# main.net
KiCad netlist of a schematic drawn in Altium Designer
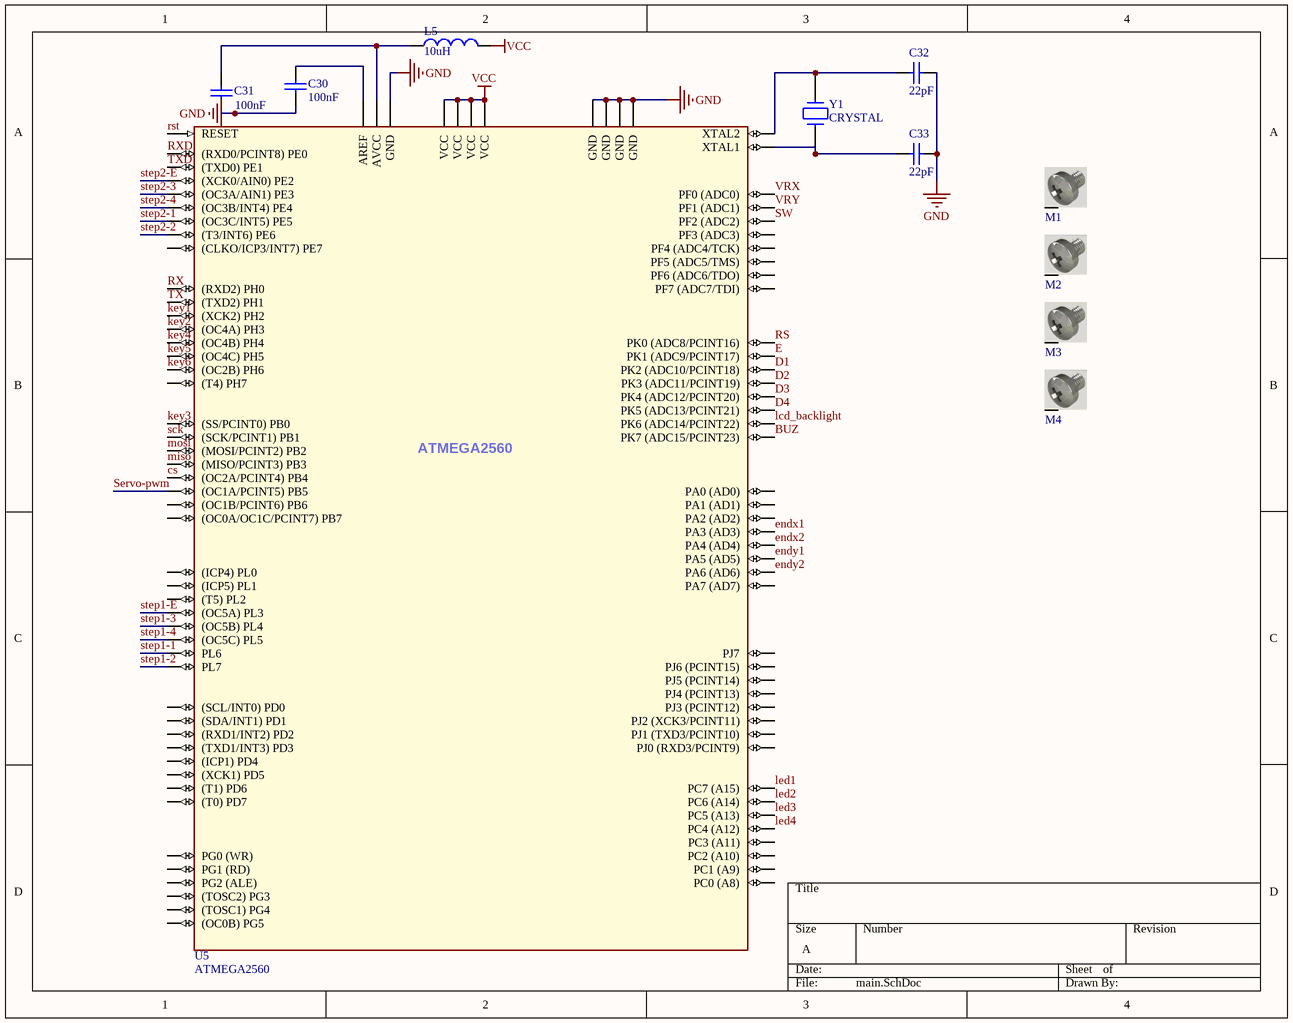
[diagram p0: main.SchDoc]

(export (version "E")
  (design (tool "Eeschema 10.0.6"))
  (components
    (comp (ref "C30")
      (value "100nF")
      (footprint "CAP 1206/3216 - 0.8MM")
      (description "CAP-100Nf")
      (fields (field (name "Comment") "Cap"))
      (libsource (lib "Altium library (www.AVRelec.com)") (part "Cap ceramic"))
    )
    (comp (ref "C31")
      (value "100nF")
      (footprint "CAP 1206/3216 - 0.8MM")
      (description "CAP-100Nf")
      (fields (field (name "Comment") "Cap"))
      (libsource (lib "Altium library (www.AVRelec.com)") (part "Cap ceramic"))
    )
    (comp (ref "C32")
      (value "22pF")
      (footprint "CAP 1206/3216 - 0.8MM")
      (description "CAP-100Nf")
      (fields (field (name "Comment") "Cap"))
      (libsource (lib "Altium library (www.AVRelec.com)") (part "Cap ceramic"))
    )
    (comp (ref "C33")
      (value "22pF")
      (footprint "CAP 1206/3216 - 0.8MM")
      (description "CAP-100Nf")
      (fields (field (name "Comment") "Cap"))
      (libsource (lib "Altium library (www.AVRelec.com)") (part "Cap ceramic"))
    )
    (comp (ref "L5")
      (value "10uH")
      (footprint "C1210_M")
      (description "Inductor")
      (fields (field (name "PUBLISHER") "Altium Limited"))
      (libsource (lib "Miscellaneous Devices") (part "Inductor"))
    )
    (comp (ref "M1")
      (value "Screw")
      (footprint "Board Screw")
      (description "Board Screw With Spacer")
      (libsource (lib "My Library") (part "Board Screw"))
    )
    (comp (ref "M2")
      (value "Screw")
      (footprint "Board Screw")
      (description "Board Screw With Spacer")
      (libsource (lib "My Library") (part "Board Screw"))
    )
    (comp (ref "M3")
      (value "Screw")
      (footprint "Board Screw")
      (description "Board Screw With Spacer")
      (libsource (lib "My Library") (part "Board Screw"))
    )
    (comp (ref "M4")
      (value "Screw")
      (footprint "Board Screw")
      (description "Board Screw With Spacer")
      (libsource (lib "My Library") (part "Board Screw"))
    )
    (comp (ref "U5")
      (value "ATMEGA2560")
      (footprint "MY_ATMEGA2560")
      (description "AVR 256K Bytes of In-System Programmable Flash Memory")
      (libsource (lib "Altium library (www.AVRelec.com)") (part "ATMEGA2560"))
    )
    (comp (ref "Y1")
      (value "CRYSTAL")
      (footprint "My_Crystal")
      (description "Crystal")
      (libsource (lib "Altium library (www.AVRelec.com)") (part "CRYSTAL"))
    )
  )
  (nets
    (net (code "1") (name "/BUZ") (class "Default")
      (node (ref "U5") (pin "82") (pinfunction "PK7_(ADC15/PCINT23)_82") (pintype "bidirectional"))
    )
    (net (code "2") (name "/D1") (class "Default")
      (node (ref "U5") (pin "87") (pinfunction "PK2_(ADC10/PCINT18)_87") (pintype "bidirectional"))
    )
    (net (code "3") (name "/D2") (class "Default")
      (node (ref "U5") (pin "86") (pinfunction "PK3_(ADC11/PCINT19)_86") (pintype "bidirectional"))
    )
    (net (code "4") (name "/D3") (class "Default")
      (node (ref "U5") (pin "85") (pinfunction "PK4_(ADC12/PCINT20)_85") (pintype "bidirectional"))
    )
    (net (code "5") (name "/D4") (class "Default")
      (node (ref "U5") (pin "84") (pinfunction "PK5_(ADC13/PCINT21)_84") (pintype "bidirectional"))
    )
    (net (code "6") (name "/E") (class "Default")
      (node (ref "U5") (pin "88") (pinfunction "PK1_(ADC9/PCINT17)_88") (pintype "bidirectional"))
    )
    (net (code "7") (name "/RS") (class "Default")
      (node (ref "U5") (pin "89") (pinfunction "PK0_(ADC8/PCINT16)_89") (pintype "bidirectional"))
    )
    (net (code "8") (name "/RX") (class "Default")
      (node (ref "U5") (pin "12") (pinfunction "(RXD2)_PH0_12") (pintype "bidirectional"))
    )
    (net (code "9") (name "/RXD") (class "Default")
      (node (ref "U5") (pin "2") (pinfunction "(RXD0/PCINT8)_PE0_2") (pintype "bidirectional"))
    )
    (net (code "10") (name "/SW") (class "Default")
      (node (ref "U5") (pin "95") (pinfunction "PF2_(ADC2)_95") (pintype "bidirectional"))
    )
    (net (code "11") (name "/Servo-pwm") (class "Default")
      (node (ref "U5") (pin "24") (pinfunction "(OC1A/PCINT5)_PB5_24") (pintype "bidirectional"))
    )
    (net (code "12") (name "/TX") (class "Default")
      (node (ref "U5") (pin "13") (pinfunction "(TXD2)_PH1_13") (pintype "bidirectional"))
    )
    (net (code "13") (name "/TXD") (class "Default")
      (node (ref "U5") (pin "3") (pinfunction "(TXD0)_PE1_3") (pintype "bidirectional"))
    )
    (net (code "14") (name "/VRX") (class "Default")
      (node (ref "U5") (pin "97") (pinfunction "PF0_(ADC0)_97") (pintype "bidirectional"))
    )
    (net (code "15") (name "/VRY") (class "Default")
      (node (ref "U5") (pin "96") (pinfunction "PF1_(ADC1)_96") (pintype "bidirectional"))
    )
    (net (code "16") (name "/cs") (class "Default")
      (node (ref "U5") (pin "23") (pinfunction "(OC2A/PCINT4)_PB4_23") (pintype "bidirectional"))
    )
    (net (code "17") (name "/endx1") (class "Default")
      (node (ref "U5") (pin "75") (pinfunction "PA3_(AD3)_75") (pintype "bidirectional"))
    )
    (net (code "18") (name "/endx2") (class "Default")
      (node (ref "U5") (pin "74") (pinfunction "PA4_(AD4)_74") (pintype "bidirectional"))
    )
    (net (code "19") (name "/endy1") (class "Default")
      (node (ref "U5") (pin "73") (pinfunction "PA5_(AD5)_73") (pintype "bidirectional"))
    )
    (net (code "20") (name "/endy2") (class "Default")
      (node (ref "U5") (pin "72") (pinfunction "PA6_(AD6)_72") (pintype "bidirectional"))
    )
    (net (code "21") (name "/key1") (class "Default")
      (node (ref "U5") (pin "14") (pinfunction "(XCK2)_PH2_14") (pintype "bidirectional"))
    )
    (net (code "22") (name "/key2") (class "Default")
      (node (ref "U5") (pin "15") (pinfunction "(OC4A)_PH3_15") (pintype "bidirectional"))
    )
    (net (code "23") (name "/key3") (class "Default")
      (node (ref "U5") (pin "19") (pinfunction "(SS/PCINT0)_PB0_19") (pintype "bidirectional"))
    )
    (net (code "24") (name "/key4") (class "Default")
      (node (ref "U5") (pin "16") (pinfunction "(OC4B)_PH4_16") (pintype "bidirectional"))
    )
    (net (code "25") (name "/key5") (class "Default")
      (node (ref "U5") (pin "17") (pinfunction "(OC4C)_PH5_17") (pintype "bidirectional"))
    )
    (net (code "26") (name "/key6") (class "Default")
      (node (ref "U5") (pin "18") (pinfunction "(OC2B)_PH6_18") (pintype "bidirectional"))
    )
    (net (code "27") (name "/lcd_backlight") (class "Default")
      (node (ref "U5") (pin "83") (pinfunction "PK6_(ADC14/PCINT22)_83") (pintype "bidirectional"))
    )
    (net (code "28") (name "/led1") (class "Default")
      (node (ref "U5") (pin "60") (pinfunction "PC7_(A15)_60") (pintype "bidirectional"))
    )
    (net (code "29") (name "/led2") (class "Default")
      (node (ref "U5") (pin "59") (pinfunction "PC6_(A14)_59") (pintype "bidirectional"))
    )
    (net (code "30") (name "/led3") (class "Default")
      (node (ref "U5") (pin "58") (pinfunction "PC5_(A13)_58") (pintype "bidirectional"))
    )
    (net (code "31") (name "/led4") (class "Default")
      (node (ref "U5") (pin "57") (pinfunction "PC4_(A12)_57") (pintype "bidirectional"))
    )
    (net (code "32") (name "/miso") (class "Default")
      (node (ref "U5") (pin "22") (pinfunction "(MISO/PCINT3)_PB3_22") (pintype "bidirectional"))
    )
    (net (code "33") (name "/mosi") (class "Default")
      (node (ref "U5") (pin "21") (pinfunction "(MOSI/PCINT2)_PB2_21") (pintype "bidirectional"))
    )
    (net (code "34") (name "/rst") (class "Default")
      (node (ref "U5") (pin "30") (pinfunction "RESET_30") (pintype "input"))
    )
    (net (code "35") (name "/sck") (class "Default")
      (node (ref "U5") (pin "20") (pinfunction "(SCK/PCINT1)_PB1_20") (pintype "bidirectional"))
    )
    (net (code "36") (name "/step1-1") (class "Default")
      (node (ref "U5") (pin "41") (pinfunction "PL6_41") (pintype "bidirectional"))
    )
    (net (code "37") (name "/step1-2") (class "Default")
      (node (ref "U5") (pin "42") (pinfunction "PL7_42") (pintype "bidirectional"))
    )
    (net (code "38") (name "/step1-3") (class "Default")
      (node (ref "U5") (pin "39") (pinfunction "(OC5B)_PL4_39") (pintype "bidirectional"))
    )
    (net (code "39") (name "/step1-4") (class "Default")
      (node (ref "U5") (pin "40") (pinfunction "(OC5C)_PL5_40") (pintype "bidirectional"))
    )
    (net (code "40") (name "/step1-E") (class "Default")
      (node (ref "U5") (pin "38") (pinfunction "(OC5A)_PL3_38") (pintype "bidirectional"))
    )
    (net (code "41") (name "/step2-1") (class "Default")
      (node (ref "U5") (pin "7") (pinfunction "(OC3C/INT5)_PE5_7") (pintype "bidirectional"))
    )
    (net (code "42") (name "/step2-2") (class "Default")
      (node (ref "U5") (pin "8") (pinfunction "(T3/INT6)_PE6_8") (pintype "bidirectional"))
    )
    (net (code "43") (name "/step2-3") (class "Default")
      (node (ref "U5") (pin "5") (pinfunction "(OC3A/AIN1)_PE3_5") (pintype "bidirectional"))
    )
    (net (code "44") (name "/step2-4") (class "Default")
      (node (ref "U5") (pin "6") (pinfunction "(OC3B/INT4)_PE4_6") (pintype "bidirectional"))
    )
    (net (code "45") (name "/step2-E") (class "Default")
      (node (ref "U5") (pin "4") (pinfunction "(XCK0/AIN0)_PE2_4") (pintype "bidirectional"))
    )
    (net (code "46") (name "GND") (class "Default")
      (node (ref "C30") (pin "1") (pinfunction "1_1") (pintype "passive"))
      (node (ref "C31") (pin "1") (pinfunction "1_1") (pintype "passive"))
      (node (ref "C32") (pin "2") (pinfunction "2_2") (pintype "passive"))
      (node (ref "C33") (pin "2") (pinfunction "2_2") (pintype "passive"))
      (node (ref "U5") (pin "11") (pinfunction "GND_11") (pintype "power_in"))
      (node (ref "U5") (pin "32") (pinfunction "GND_32") (pintype "power_in"))
      (node (ref "U5") (pin "62") (pinfunction "GND_62") (pintype "power_in"))
      (node (ref "U5") (pin "81") (pinfunction "GND_81") (pintype "power_in"))
      (node (ref "U5") (pin "99") (pinfunction "GND_99") (pintype "power_in"))
    )
    (net (code "47") (name "Net-(U5-AREF)") (class "Default")
      (node (ref "C30") (pin "2") (pinfunction "2_2") (pintype "passive"))
      (node (ref "U5") (pin "98") (pinfunction "AREF_98") (pintype "passive"))
    )
    (net (code "48") (name "Net-(U5-AVCC)") (class "Default")
      (node (ref "C31") (pin "2") (pinfunction "2_2") (pintype "passive"))
      (node (ref "L5") (pin "1") (pinfunction "1_1") (pintype "passive"))
      (node (ref "U5") (pin "100") (pinfunction "AVCC_100") (pintype "power_in"))
    )
    (net (code "49") (name "Net-(U5-XTAL1)") (class "Default")
      (node (ref "C33") (pin "1") (pinfunction "1_1") (pintype "passive"))
      (node (ref "U5") (pin "34") (pinfunction "XTAL1_34") (pintype "bidirectional"))
      (node (ref "Y1") (pin "2") (pinfunction "2_2") (pintype "passive"))
    )
    (net (code "50") (name "Net-(U5-XTAL2)") (class "Default")
      (node (ref "C32") (pin "1") (pinfunction "1_1") (pintype "passive"))
      (node (ref "U5") (pin "33") (pinfunction "XTAL2_33") (pintype "bidirectional"))
      (node (ref "Y1") (pin "1") (pinfunction "1_1") (pintype "passive"))
    )
    (net (code "51") (name "VCC") (class "Default")
      (node (ref "L5") (pin "2") (pinfunction "2_2") (pintype "passive"))
      (node (ref "U5") (pin "10") (pinfunction "VCC_10") (pintype "power_in"))
      (node (ref "U5") (pin "31") (pinfunction "VCC_31") (pintype "power_in"))
      (node (ref "U5") (pin "61") (pinfunction "VCC_61") (pintype "power_in"))
      (node (ref "U5") (pin "80") (pinfunction "VCC_80") (pintype "power_in"))
    )
    (net (code "52") (name "unconnected-(M1-PadS)") (class "Default")
      (node (ref "M1") (pin "S") (pinfunction "S_S") (pintype "passive"))
    )
    (net (code "53") (name "unconnected-(M2-PadS)") (class "Default")
      (node (ref "M2") (pin "S") (pinfunction "S_S") (pintype "passive"))
    )
    (net (code "54") (name "unconnected-(M3-PadS)") (class "Default")
      (node (ref "M3") (pin "S") (pinfunction "S_S") (pintype "passive"))
    )
    (net (code "55") (name "unconnected-(M4-PadS)") (class "Default")
      (node (ref "M4") (pin "S") (pinfunction "S_S") (pintype "passive"))
    )
    (net (code "56") (name "unconnected-(U5-(CLKO{slash}ICP3{slash}INT7)_PE7-Pad9)") (class "Default")
      (node (ref "U5") (pin "9") (pinfunction "(CLKO/ICP3/INT7)_PE7_9") (pintype "bidirectional"))
    )
    (net (code "57") (name "unconnected-(U5-(ICP1)_PD4-Pad47)") (class "Default")
      (node (ref "U5") (pin "47") (pinfunction "(ICP1)_PD4_47") (pintype "bidirectional"))
    )
    (net (code "58") (name "unconnected-(U5-(ICP4)_PL0-Pad35)") (class "Default")
      (node (ref "U5") (pin "35") (pinfunction "(ICP4)_PL0_35") (pintype "bidirectional"))
    )
    (net (code "59") (name "unconnected-(U5-(ICP5)_PL1-Pad36)") (class "Default")
      (node (ref "U5") (pin "36") (pinfunction "(ICP5)_PL1_36") (pintype "bidirectional"))
    )
    (net (code "60") (name "unconnected-(U5-(OC0A{slash}OC1C{slash}PCINT7)_PB7-Pad26)") (class "Default")
      (node (ref "U5") (pin "26") (pinfunction "(OC0A/OC1C/PCINT7)_PB7_26") (pintype "bidirectional"))
    )
    (net (code "61") (name "unconnected-(U5-(OC0B)_PG5-Pad1)") (class "Default")
      (node (ref "U5") (pin "1") (pinfunction "(OC0B)_PG5_1") (pintype "bidirectional"))
    )
    (net (code "62") (name "unconnected-(U5-(OC1B{slash}PCINT6)_PB6-Pad25)") (class "Default")
      (node (ref "U5") (pin "25") (pinfunction "(OC1B/PCINT6)_PB6_25") (pintype "bidirectional"))
    )
    (net (code "63") (name "unconnected-(U5-(RXD1{slash}INT2)_PD2-Pad45)") (class "Default")
      (node (ref "U5") (pin "45") (pinfunction "(RXD1/INT2)_PD2_45") (pintype "bidirectional"))
    )
    (net (code "64") (name "unconnected-(U5-(SCL{slash}INT0)_PD0-Pad43)") (class "Default")
      (node (ref "U5") (pin "43") (pinfunction "(SCL/INT0)_PD0_43") (pintype "bidirectional"))
    )
    (net (code "65") (name "unconnected-(U5-(SDA{slash}INT1)_PD1-Pad44)") (class "Default")
      (node (ref "U5") (pin "44") (pinfunction "(SDA/INT1)_PD1_44") (pintype "bidirectional"))
    )
    (net (code "66") (name "unconnected-(U5-(T0)_PD7-Pad50)") (class "Default")
      (node (ref "U5") (pin "50") (pinfunction "(T0)_PD7_50") (pintype "bidirectional"))
    )
    (net (code "67") (name "unconnected-(U5-(T1)_PD6-Pad49)") (class "Default")
      (node (ref "U5") (pin "49") (pinfunction "(T1)_PD6_49") (pintype "bidirectional"))
    )
    (net (code "68") (name "unconnected-(U5-(T4)_PH7-Pad27)") (class "Default")
      (node (ref "U5") (pin "27") (pinfunction "(T4)_PH7_27") (pintype "bidirectional"))
    )
    (net (code "69") (name "unconnected-(U5-(T5)_PL2-Pad37)") (class "Default")
      (node (ref "U5") (pin "37") (pinfunction "(T5)_PL2_37") (pintype "bidirectional"))
    )
    (net (code "70") (name "unconnected-(U5-(TOSC1)_PG4-Pad29)") (class "Default")
      (node (ref "U5") (pin "29") (pinfunction "(TOSC1)_PG4_29") (pintype "bidirectional"))
    )
    (net (code "71") (name "unconnected-(U5-(TOSC2)_PG3-Pad28)") (class "Default")
      (node (ref "U5") (pin "28") (pinfunction "(TOSC2)_PG3_28") (pintype "bidirectional"))
    )
    (net (code "72") (name "unconnected-(U5-(TXD1{slash}INT3)_PD3-Pad46)") (class "Default")
      (node (ref "U5") (pin "46") (pinfunction "(TXD1/INT3)_PD3_46") (pintype "bidirectional"))
    )
    (net (code "73") (name "unconnected-(U5-(XCK1)_PD5-Pad48)") (class "Default")
      (node (ref "U5") (pin "48") (pinfunction "(XCK1)_PD5_48") (pintype "bidirectional"))
    )
    (net (code "74") (name "unconnected-(U5-PA0_(AD0)-Pad78)") (class "Default")
      (node (ref "U5") (pin "78") (pinfunction "PA0_(AD0)_78") (pintype "bidirectional"))
    )
    (net (code "75") (name "unconnected-(U5-PA1_(AD1)-Pad77)") (class "Default")
      (node (ref "U5") (pin "77") (pinfunction "PA1_(AD1)_77") (pintype "bidirectional"))
    )
    (net (code "76") (name "unconnected-(U5-PA2_(AD2)-Pad76)") (class "Default")
      (node (ref "U5") (pin "76") (pinfunction "PA2_(AD2)_76") (pintype "bidirectional"))
    )
    (net (code "77") (name "unconnected-(U5-PA7_(AD7)-Pad71)") (class "Default")
      (node (ref "U5") (pin "71") (pinfunction "PA7_(AD7)_71") (pintype "bidirectional"))
    )
    (net (code "78") (name "unconnected-(U5-PC0_(A8)-Pad53)") (class "Default")
      (node (ref "U5") (pin "53") (pinfunction "PC0_(A8)_53") (pintype "bidirectional"))
    )
    (net (code "79") (name "unconnected-(U5-PC1_(A9)-Pad54)") (class "Default")
      (node (ref "U5") (pin "54") (pinfunction "PC1_(A9)_54") (pintype "bidirectional"))
    )
    (net (code "80") (name "unconnected-(U5-PC2_(A10)-Pad55)") (class "Default")
      (node (ref "U5") (pin "55") (pinfunction "PC2_(A10)_55") (pintype "bidirectional"))
    )
    (net (code "81") (name "unconnected-(U5-PC3_(A11)-Pad56)") (class "Default")
      (node (ref "U5") (pin "56") (pinfunction "PC3_(A11)_56") (pintype "bidirectional"))
    )
    (net (code "82") (name "unconnected-(U5-PF3_(ADC3)-Pad94)") (class "Default")
      (node (ref "U5") (pin "94") (pinfunction "PF3_(ADC3)_94") (pintype "bidirectional"))
    )
    (net (code "83") (name "unconnected-(U5-PF4_(ADC4{slash}TCK)-Pad93)") (class "Default")
      (node (ref "U5") (pin "93") (pinfunction "PF4_(ADC4/TCK)_93") (pintype "bidirectional"))
    )
    (net (code "84") (name "unconnected-(U5-PF5_(ADC5{slash}TMS)-Pad92)") (class "Default")
      (node (ref "U5") (pin "92") (pinfunction "PF5_(ADC5/TMS)_92") (pintype "bidirectional"))
    )
    (net (code "85") (name "unconnected-(U5-PF6_(ADC6{slash}TDO)-Pad91)") (class "Default")
      (node (ref "U5") (pin "91") (pinfunction "PF6_(ADC6/TDO)_91") (pintype "bidirectional"))
    )
    (net (code "86") (name "unconnected-(U5-PF7_(ADC7{slash}TDI)-Pad90)") (class "Default")
      (node (ref "U5") (pin "90") (pinfunction "PF7_(ADC7/TDI)_90") (pintype "bidirectional"))
    )
    (net (code "87") (name "unconnected-(U5-PG0_(WR)-Pad51)") (class "Default")
      (node (ref "U5") (pin "51") (pinfunction "PG0_(WR)_51") (pintype "bidirectional"))
    )
    (net (code "88") (name "unconnected-(U5-PG1_(RD)-Pad52)") (class "Default")
      (node (ref "U5") (pin "52") (pinfunction "PG1_(RD)_52") (pintype "bidirectional"))
    )
    (net (code "89") (name "unconnected-(U5-PG2_(ALE)-Pad70)") (class "Default")
      (node (ref "U5") (pin "70") (pinfunction "PG2_(ALE)_70") (pintype "bidirectional"))
    )
    (net (code "90") (name "unconnected-(U5-PJ0_(RXD3{slash}PCINT9)-Pad63)") (class "Default")
      (node (ref "U5") (pin "63") (pinfunction "PJ0_(RXD3/PCINT9)_63") (pintype "bidirectional"))
    )
    (net (code "91") (name "unconnected-(U5-PJ1_(TXD3{slash}PCINT10)-Pad64)") (class "Default")
      (node (ref "U5") (pin "64") (pinfunction "PJ1_(TXD3/PCINT10)_64") (pintype "bidirectional"))
    )
    (net (code "92") (name "unconnected-(U5-PJ2_(XCK3{slash}PCINT11)-Pad65)") (class "Default")
      (node (ref "U5") (pin "65") (pinfunction "PJ2_(XCK3/PCINT11)_65") (pintype "bidirectional"))
    )
    (net (code "93") (name "unconnected-(U5-PJ3_(PCINT12)-Pad66)") (class "Default")
      (node (ref "U5") (pin "66") (pinfunction "PJ3_(PCINT12)_66") (pintype "bidirectional"))
    )
    (net (code "94") (name "unconnected-(U5-PJ4_(PCINT13)-Pad67)") (class "Default")
      (node (ref "U5") (pin "67") (pinfunction "PJ4_(PCINT13)_67") (pintype "bidirectional"))
    )
    (net (code "95") (name "unconnected-(U5-PJ5_(PCINT14)-Pad68)") (class "Default")
      (node (ref "U5") (pin "68") (pinfunction "PJ5_(PCINT14)_68") (pintype "bidirectional"))
    )
    (net (code "96") (name "unconnected-(U5-PJ6_(PCINT15)-Pad69)") (class "Default")
      (node (ref "U5") (pin "69") (pinfunction "PJ6_(PCINT15)_69") (pintype "bidirectional"))
    )
    (net (code "97") (name "unconnected-(U5-PJ7-Pad79)") (class "Default")
      (node (ref "U5") (pin "79") (pinfunction "PJ7_79") (pintype "bidirectional"))
    )
  )
)
